# 2_digital_a.net
KiCad netlist of a schematic drawn in EAGLE
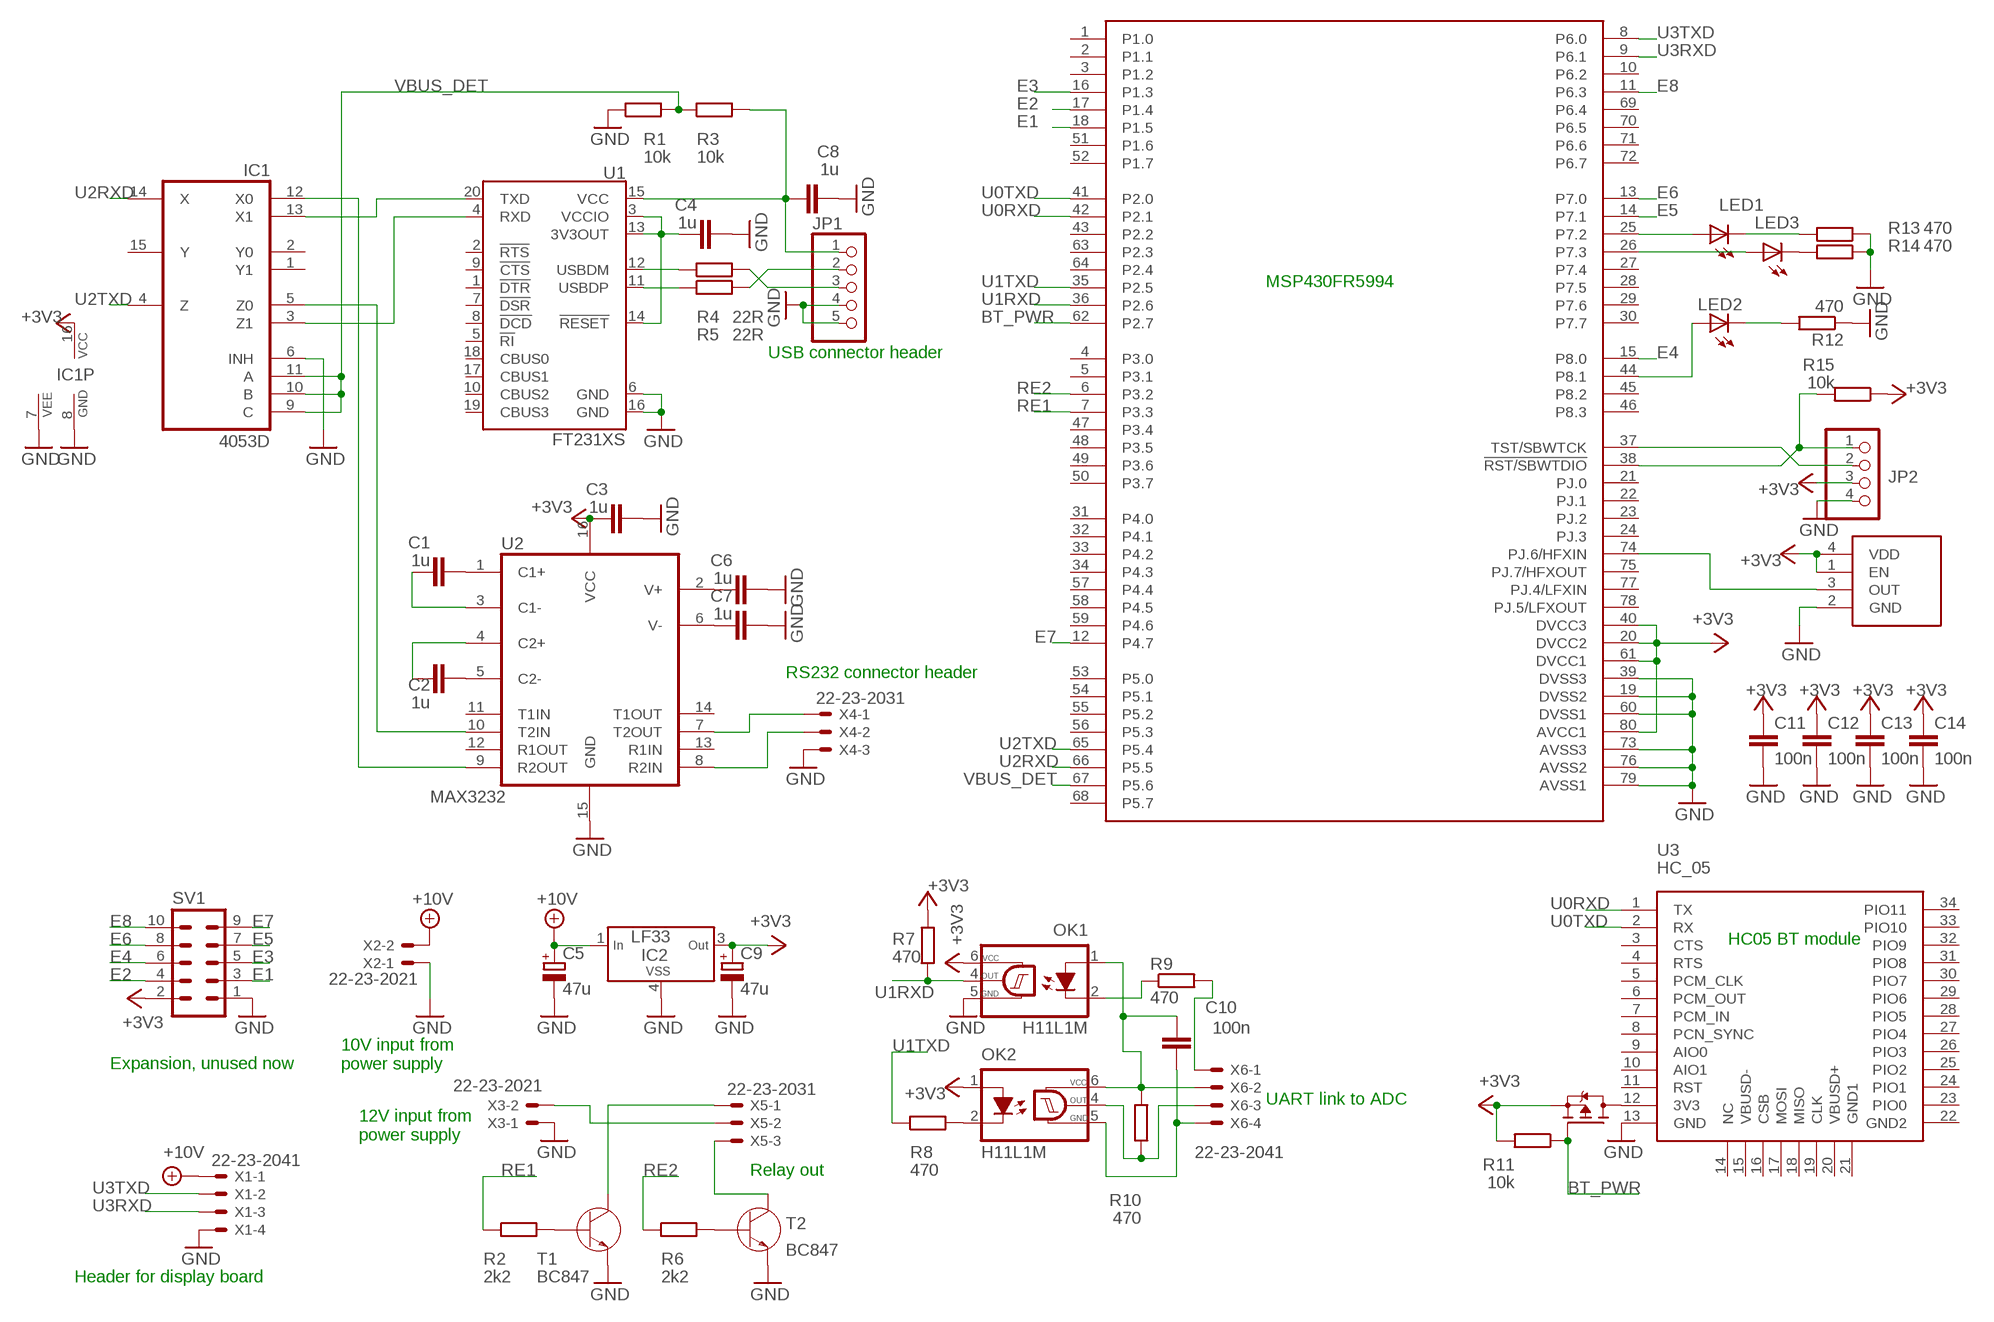
[diagram p0: schematic, sheet 1]

(export (version "E")
  (design (tool "Eeschema 10.0.6"))
  (components
    (comp (ref "C1")
      (value "1u")
      (footprint "eagle-import:R0805")
      (libsource (lib "eagle-import") (part "C_0806"))
    )
    (comp (ref "C2")
      (value "1u")
      (footprint "eagle-import:R0805")
      (libsource (lib "eagle-import") (part "C_0806"))
    )
    (comp (ref "C3")
      (value "1u")
      (footprint "eagle-import:R0805")
      (libsource (lib "eagle-import") (part "C_0806"))
    )
    (comp (ref "C4")
      (value "1u")
      (footprint "eagle-import:R0805")
      (libsource (lib "eagle-import") (part "C_0806"))
    )
    (comp (ref "C5")
      (value "47u")
      (footprint "eagle-import:SMC_C")
      (libsource (lib "eagle-import") (part "CPOL-EUSMCC"))
    )
    (comp (ref "C6")
      (value "1u")
      (footprint "eagle-import:R0805")
      (libsource (lib "eagle-import") (part "C_0806"))
    )
    (comp (ref "C7")
      (value "1u")
      (footprint "eagle-import:R0805")
      (libsource (lib "eagle-import") (part "C_0806"))
    )
    (comp (ref "C8")
      (value "1u")
      (footprint "eagle-import:R0805")
      (libsource (lib "eagle-import") (part "C_0806"))
    )
    (comp (ref "C9")
      (value "47u")
      (footprint "eagle-import:SMC_C")
      (libsource (lib "eagle-import") (part "CPOL-EUSMCC"))
    )
    (comp (ref "C10")
      (value "100n")
      (footprint "eagle-import:0603")
      (libsource (lib "eagle-import") (part "C_0603"))
    )
    (comp (ref "C11")
      (value "100n")
      (footprint "eagle-import:0603")
      (libsource (lib "eagle-import") (part "C_0603"))
    )
    (comp (ref "C12")
      (value "100n")
      (footprint "eagle-import:0603")
      (libsource (lib "eagle-import") (part "C_0603"))
    )
    (comp (ref "C13")
      (value "100n")
      (footprint "eagle-import:0603")
      (libsource (lib "eagle-import") (part "C_0603"))
    )
    (comp (ref "C14")
      (value "100n")
      (footprint "eagle-import:0603")
      (libsource (lib "eagle-import") (part "C_0603"))
    )
    (comp (ref "IC1")
      (value "4053D")
      (footprint "eagle-import:SO16")
      (libsource (lib "eagle-import") (part "4053D"))
    )
    (comp (ref "IC2")
      (value "LF33")
      (footprint "eagle-import:DPAK")
      (libsource (lib "eagle-import") (part "LF33-DPAK"))
    )
    (comp (ref "IC3")
      (value "MSP430FR5994")
      (footprint "eagle-import:QFP_05_80")
      (libsource (lib "eagle-import") (part "MSP430FR5994"))
    )
    (comp (ref "JP1")
      (value "PINHD-1X05_2.54")
      (footprint "eagle-import:1X05")
      (libsource (lib "eagle-import") (part "PINHD-1X05_2.54"))
    )
    (comp (ref "JP2")
      (value "PINHD-1X04_2.54")
      (footprint "eagle-import:1X04")
      (libsource (lib "eagle-import") (part "PINHD-1X04_2.54"))
    )
    (comp (ref "LED1")
      (value "LEDCHIPLED_0805")
      (footprint "eagle-import:CHIPLED_0805")
      (libsource (lib "eagle-import") (part "LEDCHIPLED_0805"))
    )
    (comp (ref "LED2")
      (value "LEDCHIPLED_0805")
      (footprint "eagle-import:CHIPLED_0805")
      (libsource (lib "eagle-import") (part "LEDCHIPLED_0805"))
    )
    (comp (ref "LED3")
      (value "LEDCHIPLED_0805")
      (footprint "eagle-import:CHIPLED_0805")
      (libsource (lib "eagle-import") (part "LEDCHIPLED_0805"))
    )
    (comp (ref "O1")
      (value "OSC5032")
      (footprint "eagle-import:OSC_5032")
      (libsource (lib "eagle-import") (part "OSC5032"))
    )
    (comp (ref "OK1")
      (value "H11L1M")
      (footprint "eagle-import:DIL06")
      (libsource (lib "eagle-import") (part "H11LM1"))
    )
    (comp (ref "OK2")
      (value "H11L1M")
      (footprint "eagle-import:DIL06")
      (libsource (lib "eagle-import") (part "H11LM1"))
    )
    (comp (ref "R1")
      (value "10k")
      (footprint "eagle-import:R0805")
      (libsource (lib "eagle-import") (part "R_0805"))
    )
    (comp (ref "R2")
      (value "2k2")
      (footprint "eagle-import:R0805")
      (libsource (lib "eagle-import") (part "R_0805"))
    )
    (comp (ref "R3")
      (value "10k")
      (footprint "eagle-import:R0805")
      (libsource (lib "eagle-import") (part "R_0805"))
    )
    (comp (ref "R4")
      (value "22R")
      (footprint "eagle-import:R0805")
      (libsource (lib "eagle-import") (part "R_0805"))
    )
    (comp (ref "R5")
      (value "22R")
      (footprint "eagle-import:R0805")
      (libsource (lib "eagle-import") (part "R_0805"))
    )
    (comp (ref "R6")
      (value "2k2")
      (footprint "eagle-import:R0805")
      (libsource (lib "eagle-import") (part "R_0805"))
    )
    (comp (ref "R7")
      (value "470")
      (footprint "eagle-import:R0805")
      (libsource (lib "eagle-import") (part "R_0805"))
    )
    (comp (ref "R8")
      (value "470")
      (footprint "eagle-import:R0805")
      (libsource (lib "eagle-import") (part "R_0805"))
    )
    (comp (ref "R9")
      (value "470")
      (footprint "eagle-import:R0805")
      (libsource (lib "eagle-import") (part "R_0805"))
    )
    (comp (ref "R10")
      (value "470")
      (footprint "eagle-import:R0805")
      (libsource (lib "eagle-import") (part "R_0805"))
    )
    (comp (ref "R11")
      (value "10k")
      (footprint "eagle-import:R0805")
      (libsource (lib "eagle-import") (part "R_0805"))
    )
    (comp (ref "R12")
      (value "470")
      (footprint "eagle-import:R0805")
      (libsource (lib "eagle-import") (part "R_0805"))
    )
    (comp (ref "R13")
      (value "470")
      (footprint "eagle-import:R0805")
      (libsource (lib "eagle-import") (part "R_0805"))
    )
    (comp (ref "R14")
      (value "470")
      (footprint "eagle-import:R0805")
      (libsource (lib "eagle-import") (part "R_0805"))
    )
    (comp (ref "R15")
      (value "10k")
      (footprint "eagle-import:R0805")
      (libsource (lib "eagle-import") (part "R_0805"))
    )
    (comp (ref "SV1")
      (value "ML10")
      (footprint "eagle-import:ML10")
      (libsource (lib "eagle-import") (part "ML10"))
    )
    (comp (ref "T1")
      (value "BC847")
      (footprint "eagle-import:SOT23")
      (libsource (lib "eagle-import") (part "BC847"))
    )
    (comp (ref "T2")
      (value "BC847")
      (footprint "eagle-import:SOT23")
      (libsource (lib "eagle-import") (part "BC847"))
    )
    (comp (ref "U$1")
      (value "Si2333")
      (footprint "eagle-import:SOT23-3")
      (libsource (lib "eagle-import") (part "BSS84"))
    )
    (comp (ref "U1")
      (value "FT231XS")
      (footprint "eagle-import:SSOP20_L")
      (libsource (lib "eagle-import") (part "FT231XS"))
    )
    (comp (ref "U2")
      (value "MAX3232")
      (footprint "eagle-import:SO016")
      (libsource (lib "eagle-import") (part "MAX232SOIC16"))
    )
    (comp (ref "U3")
      (value "HC_05")
      (footprint "eagle-import:BLUETOOTH_SMD")
      (libsource (lib "eagle-import") (part "HC_05"))
    )
    (comp (ref "X1")
      (value "22-23-2041")
      (footprint "eagle-import:22-23-2041")
      (fields (field (name "MF") "MOLEX"))
      (libsource (lib "eagle-import") (part "22-23-2041"))
    )
    (comp (ref "X2")
      (value "22-23-2021")
      (footprint "eagle-import:22-23-2021")
      (fields (field (name "MF") "MOLEX"))
      (libsource (lib "eagle-import") (part "22-23-2021"))
    )
    (comp (ref "X3")
      (value "22-23-2021")
      (footprint "eagle-import:22-23-2021")
      (fields (field (name "MF") "MOLEX"))
      (libsource (lib "eagle-import") (part "22-23-2021"))
    )
    (comp (ref "X4")
      (value "22-23-2031")
      (footprint "eagle-import:22-23-2031")
      (fields (field (name "MF") "MOLEX"))
      (libsource (lib "eagle-import") (part "22-23-2031"))
    )
    (comp (ref "X5")
      (value "22-23-2031")
      (footprint "eagle-import:22-23-2031")
      (fields (field (name "MF") "MOLEX"))
      (libsource (lib "eagle-import") (part "22-23-2031"))
    )
    (comp (ref "X6")
      (value "22-23-2041")
      (footprint "eagle-import:22-23-2041")
      (fields (field (name "MF") "MOLEX"))
      (libsource (lib "eagle-import") (part "22-23-2041"))
    )
  )
  (nets
    (net (code "1") (name "+3V3") (class "Default")
      (node (ref "C11") (pin "1") (pinfunction "1_1") (pintype "passive"))
      (node (ref "C12") (pin "1") (pinfunction "1_1") (pintype "passive"))
      (node (ref "C13") (pin "1") (pinfunction "1_1") (pintype "passive"))
      (node (ref "C14") (pin "1") (pinfunction "1_1") (pintype "passive"))
      (node (ref "C3") (pin "1") (pinfunction "1_1") (pintype "passive"))
      (node (ref "C9") (pin "+") (pinfunction "+_+") (pintype "passive"))
      (node (ref "IC1") (pin "16") (pinfunction "VCC_16") (pintype "power_in"))
      (node (ref "IC2") (pin "3") (pinfunction "OUT_3") (pintype "output"))
      (node (ref "IC3") (pin "20") (pinfunction "DVCC2_20") (pintype "bidirectional"))
      (node (ref "IC3") (pin "40") (pinfunction "DVCC3_40") (pintype "bidirectional"))
      (node (ref "IC3") (pin "61") (pinfunction "DVCC1_61") (pintype "bidirectional"))
      (node (ref "IC3") (pin "80") (pinfunction "AVCC1_80") (pintype "bidirectional"))
      (node (ref "JP2") (pin "3") (pinfunction "3_3") (pintype "passive"))
      (node (ref "O1") (pin "1") (pinfunction "EN_1") (pintype "bidirectional"))
      (node (ref "O1") (pin "4") (pinfunction "VDD_4") (pintype "bidirectional"))
      (node (ref "OK1") (pin "6") (pinfunction "VCC_6") (pintype "power_in"))
      (node (ref "OK2") (pin "1") (pinfunction "A_1") (pintype "passive"))
      (node (ref "R11") (pin "2") (pinfunction "2_2") (pintype "passive"))
      (node (ref "R15") (pin "1") (pinfunction "1_1") (pintype "passive"))
      (node (ref "R7") (pin "1") (pinfunction "1_1") (pintype "passive"))
      (node (ref "SV1") (pin "2") (pinfunction "2_2") (pintype "passive"))
      (node (ref "U$1") (pin "2") (pinfunction "S_2") (pintype "passive"))
      (node (ref "U2") (pin "16") (pinfunction "VCC_16") (pintype "bidirectional"))
    )
    (net (code "2") (name "+10V") (class "Default")
      (node (ref "C5") (pin "+") (pinfunction "+_+") (pintype "passive"))
      (node (ref "IC2") (pin "1") (pinfunction "IN_1") (pintype "input"))
      (node (ref "X1") (pin "1") (pinfunction "S_1") (pintype "passive"))
      (node (ref "X2") (pin "2") (pinfunction "S_2") (pintype "passive"))
    )
    (net (code "3") (name "/BT_PWR") (class "Default")
      (node (ref "IC3") (pin "62") (pinfunction "P2.7_62") (pintype "bidirectional"))
      (node (ref "R11") (pin "1") (pinfunction "1_1") (pintype "passive"))
      (node (ref "U$1") (pin "1") (pinfunction "G_1") (pintype "passive"))
    )
    (net (code "4") (name "/E1") (class "Default")
      (node (ref "IC3") (pin "18") (pinfunction "P1.5_18") (pintype "bidirectional"))
      (node (ref "SV1") (pin "3") (pinfunction "3_3") (pintype "passive"))
    )
    (net (code "5") (name "/E2") (class "Default")
      (node (ref "IC3") (pin "17") (pinfunction "P1.4_17") (pintype "bidirectional"))
      (node (ref "SV1") (pin "4") (pinfunction "4_4") (pintype "passive"))
    )
    (net (code "6") (name "/E3") (class "Default")
      (node (ref "IC3") (pin "16") (pinfunction "P1.3_16") (pintype "bidirectional"))
      (node (ref "SV1") (pin "5") (pinfunction "5_5") (pintype "passive"))
    )
    (net (code "7") (name "/E4") (class "Default")
      (node (ref "IC3") (pin "15") (pinfunction "P8.0_15") (pintype "bidirectional"))
      (node (ref "SV1") (pin "6") (pinfunction "6_6") (pintype "passive"))
    )
    (net (code "8") (name "/E5") (class "Default")
      (node (ref "IC3") (pin "14") (pinfunction "P7.1_14") (pintype "bidirectional"))
      (node (ref "SV1") (pin "7") (pinfunction "7_7") (pintype "passive"))
    )
    (net (code "9") (name "/E6") (class "Default")
      (node (ref "IC3") (pin "13") (pinfunction "P7.0_13") (pintype "bidirectional"))
      (node (ref "SV1") (pin "8") (pinfunction "8_8") (pintype "passive"))
    )
    (net (code "10") (name "/E7") (class "Default")
      (node (ref "IC3") (pin "12") (pinfunction "P4.7_12") (pintype "bidirectional"))
      (node (ref "SV1") (pin "9") (pinfunction "9_9") (pintype "passive"))
    )
    (net (code "11") (name "/E8") (class "Default")
      (node (ref "IC3") (pin "11") (pinfunction "P6.3_11") (pintype "bidirectional"))
      (node (ref "SV1") (pin "10") (pinfunction "10_10") (pintype "passive"))
    )
    (net (code "12") (name "/RE1") (class "Default")
      (node (ref "IC3") (pin "7") (pinfunction "P3.3_7") (pintype "bidirectional"))
      (node (ref "R2") (pin "1") (pinfunction "1_1") (pintype "passive"))
    )
    (net (code "13") (name "/RE2") (class "Default")
      (node (ref "IC3") (pin "6") (pinfunction "P3.2_6") (pintype "bidirectional"))
      (node (ref "R6") (pin "1") (pinfunction "1_1") (pintype "passive"))
    )
    (net (code "14") (name "/U0RXD") (class "Default")
      (node (ref "IC3") (pin "42") (pinfunction "P2.1_42") (pintype "bidirectional"))
      (node (ref "U3") (pin "1") (pinfunction "TX_1") (pintype "bidirectional"))
    )
    (net (code "15") (name "/U0TXD") (class "Default")
      (node (ref "IC3") (pin "41") (pinfunction "P2.0_41") (pintype "bidirectional"))
      (node (ref "U3") (pin "2") (pinfunction "RX_2") (pintype "bidirectional"))
    )
    (net (code "16") (name "/U1RXD") (class "Default")
      (node (ref "IC3") (pin "36") (pinfunction "P2.6_36") (pintype "bidirectional"))
      (node (ref "OK1") (pin "4") (pinfunction "OUT_4") (pintype "output"))
      (node (ref "R7") (pin "2") (pinfunction "2_2") (pintype "passive"))
    )
    (net (code "17") (name "/U1TXD") (class "Default")
      (node (ref "IC3") (pin "35") (pinfunction "P2.5_35") (pintype "bidirectional"))
      (node (ref "R8") (pin "1") (pinfunction "1_1") (pintype "passive"))
    )
    (net (code "18") (name "/U2RXD") (class "Default")
      (node (ref "IC1") (pin "14") (pinfunction "X_14") (pintype "bidirectional"))
      (node (ref "IC3") (pin "66") (pinfunction "P5.5_66") (pintype "bidirectional"))
    )
    (net (code "19") (name "/U2TXD") (class "Default")
      (node (ref "IC1") (pin "4") (pinfunction "Z_4") (pintype "bidirectional"))
      (node (ref "IC3") (pin "65") (pinfunction "P5.4_65") (pintype "bidirectional"))
    )
    (net (code "20") (name "/U3RXD") (class "Default")
      (node (ref "IC3") (pin "9") (pinfunction "P6.1_9") (pintype "bidirectional"))
      (node (ref "X1") (pin "3") (pinfunction "S_3") (pintype "passive"))
    )
    (net (code "21") (name "/U3TXD") (class "Default")
      (node (ref "IC3") (pin "8") (pinfunction "P6.0_8") (pintype "bidirectional"))
      (node (ref "X1") (pin "2") (pinfunction "S_2") (pintype "passive"))
    )
    (net (code "22") (name "/VBUS_DET") (class "Default")
      (node (ref "IC1") (pin "10") (pinfunction "B_10") (pintype "input"))
      (node (ref "IC1") (pin "11") (pinfunction "A_11") (pintype "input"))
      (node (ref "IC1") (pin "9") (pinfunction "C_9") (pintype "input"))
      (node (ref "IC3") (pin "67") (pinfunction "P5.6_67") (pintype "bidirectional"))
      (node (ref "R1") (pin "2") (pinfunction "2_2") (pintype "passive"))
      (node (ref "R3") (pin "1") (pinfunction "1_1") (pintype "passive"))
    )
    (net (code "23") (name "GND") (class "Default")
      (node (ref "C11") (pin "2") (pinfunction "2_2") (pintype "passive"))
      (node (ref "C12") (pin "2") (pinfunction "2_2") (pintype "passive"))
      (node (ref "C13") (pin "2") (pinfunction "2_2") (pintype "passive"))
      (node (ref "C14") (pin "2") (pinfunction "2_2") (pintype "passive"))
      (node (ref "C3") (pin "2") (pinfunction "2_2") (pintype "passive"))
      (node (ref "C4") (pin "2") (pinfunction "2_2") (pintype "passive"))
      (node (ref "C5") (pin "-") (pinfunction "-_-") (pintype "passive"))
      (node (ref "C6") (pin "2") (pinfunction "2_2") (pintype "passive"))
      (node (ref "C7") (pin "2") (pinfunction "2_2") (pintype "passive"))
      (node (ref "C8") (pin "2") (pinfunction "2_2") (pintype "passive"))
      (node (ref "C9") (pin "-") (pinfunction "-_-") (pintype "passive"))
      (node (ref "IC1") (pin "6") (pinfunction "INH_6") (pintype "input"))
      (node (ref "IC1") (pin "7") (pinfunction "VEE_7") (pintype "power_in"))
      (node (ref "IC1") (pin "8") (pinfunction "GND_8") (pintype "power_in"))
      (node (ref "IC2") (pin "4") (pinfunction "VSS_4") (pintype "input"))
      (node (ref "IC3") (pin "19") (pinfunction "DVSS2_19") (pintype "bidirectional"))
      (node (ref "IC3") (pin "39") (pinfunction "DVSS3_39") (pintype "bidirectional"))
      (node (ref "IC3") (pin "60") (pinfunction "DVSS1_60") (pintype "bidirectional"))
      (node (ref "IC3") (pin "73") (pinfunction "AVSS3_73") (pintype "bidirectional"))
      (node (ref "IC3") (pin "76") (pinfunction "AVSS2_76") (pintype "bidirectional"))
      (node (ref "IC3") (pin "79") (pinfunction "AVSS1_79") (pintype "bidirectional"))
      (node (ref "JP1") (pin "4") (pinfunction "4_4") (pintype "passive"))
      (node (ref "JP1") (pin "5") (pinfunction "5_5") (pintype "passive"))
      (node (ref "JP2") (pin "4") (pinfunction "4_4") (pintype "passive"))
      (node (ref "O1") (pin "2") (pinfunction "GND_2") (pintype "bidirectional"))
      (node (ref "OK1") (pin "5") (pinfunction "GND_5") (pintype "power_in"))
      (node (ref "R1") (pin "1") (pinfunction "1_1") (pintype "passive"))
      (node (ref "R12") (pin "1") (pinfunction "1_1") (pintype "passive"))
      (node (ref "R13") (pin "1") (pinfunction "1_1") (pintype "passive"))
      (node (ref "R14") (pin "1") (pinfunction "1_1") (pintype "passive"))
      (node (ref "SV1") (pin "1") (pinfunction "1_1") (pintype "passive"))
      (node (ref "T1") (pin "2") (pinfunction "E_2") (pintype "passive"))
      (node (ref "T2") (pin "2") (pinfunction "E_2") (pintype "passive"))
      (node (ref "U1") (pin "16") (pinfunction "GND_16") (pintype "bidirectional"))
      (node (ref "U1") (pin "6") (pinfunction "GND_6") (pintype "bidirectional"))
      (node (ref "U2") (pin "15") (pinfunction "GND_15") (pintype "bidirectional"))
      (node (ref "U3") (pin "13") (pinfunction "GND_13") (pintype "bidirectional"))
      (node (ref "X1") (pin "4") (pinfunction "S_4") (pintype "passive"))
      (node (ref "X2") (pin "1") (pinfunction "S_1") (pintype "passive"))
      (node (ref "X3") (pin "1") (pinfunction "S_1") (pintype "passive"))
      (node (ref "X4") (pin "3") (pinfunction "S_3") (pintype "passive"))
    )
    (net (code "24") (name "Net-(IC1A-X0)") (class "Default")
      (node (ref "IC1") (pin "12") (pinfunction "X0_12") (pintype "bidirectional"))
      (node (ref "U2") (pin "9") (pinfunction "R2OUT_9") (pintype "output"))
    )
    (net (code "25") (name "Net-(IC1A-X1)") (class "Default")
      (node (ref "IC1") (pin "13") (pinfunction "X1_13") (pintype "bidirectional"))
      (node (ref "U1") (pin "20") (pinfunction "TXD_20") (pintype "bidirectional"))
    )
    (net (code "26") (name "Net-(IC1A-Z0)") (class "Default")
      (node (ref "IC1") (pin "5") (pinfunction "Z0_5") (pintype "bidirectional"))
      (node (ref "U2") (pin "10") (pinfunction "T2IN_10") (pintype "input"))
    )
    (net (code "27") (name "Net-(IC1A-Z1)") (class "Default")
      (node (ref "IC1") (pin "3") (pinfunction "Z1_3") (pintype "bidirectional"))
      (node (ref "U1") (pin "4") (pinfunction "RXD_4") (pintype "bidirectional"))
    )
    (net (code "28") (name "Net-(IC3-P7.2)") (class "Default")
      (node (ref "IC3") (pin "25") (pinfunction "P7.2_25") (pintype "bidirectional"))
      (node (ref "LED1") (pin "A") (pinfunction "A_A") (pintype "passive"))
    )
    (net (code "29") (name "Net-(IC3-P7.3)") (class "Default")
      (node (ref "IC3") (pin "26") (pinfunction "P7.3_26") (pintype "bidirectional"))
      (node (ref "LED3") (pin "A") (pinfunction "A_A") (pintype "passive"))
    )
    (net (code "30") (name "Net-(IC3-P8.1)") (class "Default")
      (node (ref "IC3") (pin "44") (pinfunction "P8.1_44") (pintype "bidirectional"))
      (node (ref "LED2") (pin "A") (pinfunction "A_A") (pintype "passive"))
    )
    (net (code "31") (name "Net-(IC3-PJ.6{slash}HFXIN)") (class "Default")
      (node (ref "IC3") (pin "74") (pinfunction "PJ.6/HFXIN_74") (pintype "bidirectional"))
      (node (ref "O1") (pin "3") (pinfunction "OUT_3") (pintype "bidirectional"))
    )
    (net (code "32") (name "Net-(IC3-TST{slash}SBWTCK)") (class "Default")
      (node (ref "IC3") (pin "37") (pinfunction "TST/SBWTCK_37") (pintype "bidirectional"))
      (node (ref "JP2") (pin "2") (pinfunction "2_2") (pintype "passive"))
    )
    (net (code "33") (name "Net-(IC3-~{RST{slash}SBWTDIO})") (class "Default")
      (node (ref "IC3") (pin "38") (pinfunction "~{RST/SBWTDIO}_38") (pintype "bidirectional"))
      (node (ref "JP2") (pin "1") (pinfunction "1_1") (pintype "passive"))
      (node (ref "R15") (pin "2") (pinfunction "2_2") (pintype "passive"))
    )
    (net (code "34") (name "Net-(JP1-Pad2)") (class "Default")
      (node (ref "JP1") (pin "2") (pinfunction "2_2") (pintype "passive"))
      (node (ref "R5") (pin "2") (pinfunction "2_2") (pintype "passive"))
    )
    (net (code "35") (name "Net-(JP1-Pad3)") (class "Default")
      (node (ref "JP1") (pin "3") (pinfunction "3_3") (pintype "passive"))
      (node (ref "R4") (pin "2") (pinfunction "2_2") (pintype "passive"))
    )
    (net (code "36") (name "Net-(LED1-PadC)") (class "Default")
      (node (ref "LED1") (pin "C") (pinfunction "C_C") (pintype "passive"))
      (node (ref "R13") (pin "2") (pinfunction "2_2") (pintype "passive"))
    )
    (net (code "37") (name "Net-(LED2-PadC)") (class "Default")
      (node (ref "LED2") (pin "C") (pinfunction "C_C") (pintype "passive"))
      (node (ref "R12") (pin "2") (pinfunction "2_2") (pintype "passive"))
    )
    (net (code "38") (name "Net-(LED3-PadC)") (class "Default")
      (node (ref "LED3") (pin "C") (pinfunction "C_C") (pintype "passive"))
      (node (ref "R14") (pin "2") (pinfunction "2_2") (pintype "passive"))
    )
    (net (code "39") (name "Net-(OK1-A)") (class "Default")
      (node (ref "C10") (pin "1") (pinfunction "1_1") (pintype "passive"))
      (node (ref "OK1") (pin "1") (pinfunction "A_1") (pintype "passive"))
      (node (ref "OK2") (pin "6") (pinfunction "VCC_6") (pintype "power_in"))
      (node (ref "R10") (pin "2") (pinfunction "2_2") (pintype "passive"))
      (node (ref "X6") (pin "2") (pinfunction "S_2") (pintype "passive"))
    )
    (net (code "40") (name "Net-(OK1-C)") (class "Default")
      (node (ref "OK1") (pin "2") (pinfunction "C_2") (pintype "passive"))
      (node (ref "R9") (pin "1") (pinfunction "1_1") (pintype "passive"))
    )
    (net (code "41") (name "Net-(OK2-C)") (class "Default")
      (node (ref "OK2") (pin "2") (pinfunction "C_2") (pintype "passive"))
      (node (ref "R8") (pin "2") (pinfunction "2_2") (pintype "passive"))
    )
    (net (code "42") (name "Net-(OK2-GND)") (class "Default")
      (node (ref "C10") (pin "2") (pinfunction "2_2") (pintype "passive"))
      (node (ref "OK2") (pin "5") (pinfunction "GND_5") (pintype "power_in"))
      (node (ref "X6") (pin "4") (pinfunction "S_4") (pintype "passive"))
    )
    (net (code "43") (name "Net-(OK2-OUT)") (class "Default")
      (node (ref "OK2") (pin "4") (pinfunction "OUT_4") (pintype "output"))
      (node (ref "R10") (pin "1") (pinfunction "1_1") (pintype "passive"))
      (node (ref "X6") (pin "3") (pinfunction "S_3") (pintype "passive"))
    )
    (net (code "44") (name "Net-(T1-B)") (class "Default")
      (node (ref "R2") (pin "2") (pinfunction "2_2") (pintype "passive"))
      (node (ref "T1") (pin "1") (pinfunction "B_1") (pintype "passive"))
    )
    (net (code "45") (name "Net-(T1-C)") (class "Default")
      (node (ref "T1") (pin "3") (pinfunction "C_3") (pintype "passive"))
      (node (ref "X5") (pin "1") (pinfunction "S_1") (pintype "passive"))
    )
    (net (code "46") (name "Net-(T2-B)") (class "Default")
      (node (ref "R6") (pin "2") (pinfunction "2_2") (pintype "passive"))
      (node (ref "T2") (pin "1") (pinfunction "B_1") (pintype "passive"))
    )
    (net (code "47") (name "Net-(T2-C)") (class "Default")
      (node (ref "T2") (pin "3") (pinfunction "C_3") (pintype "passive"))
      (node (ref "X5") (pin "3") (pinfunction "S_3") (pintype "passive"))
    )
    (net (code "48") (name "Net-(U$1-D)") (class "Default")
      (node (ref "U$1") (pin "3") (pinfunction "D_3") (pintype "passive"))
      (node (ref "U3") (pin "12") (pinfunction "3V3_12") (pintype "bidirectional"))
    )
    (net (code "49") (name "Net-(U1-3V3OUT)") (class "Default")
      (node (ref "C4") (pin "1") (pinfunction "1_1") (pintype "passive"))
      (node (ref "U1") (pin "13") (pinfunction "3V3OUT_13") (pintype "bidirectional"))
      (node (ref "U1") (pin "14") (pinfunction "~{RESET}_14") (pintype "bidirectional"))
      (node (ref "U1") (pin "3") (pinfunction "VCCIO_3") (pintype "bidirectional"))
    )
    (net (code "50") (name "Net-(U1-USBDM)") (class "Default")
      (node (ref "R4") (pin "1") (pinfunction "1_1") (pintype "passive"))
      (node (ref "U1") (pin "12") (pinfunction "USBDM_12") (pintype "bidirectional"))
    )
    (net (code "51") (name "Net-(U1-USBDP)") (class "Default")
      (node (ref "R5") (pin "1") (pinfunction "1_1") (pintype "passive"))
      (node (ref "U1") (pin "11") (pinfunction "USBDP_11") (pintype "bidirectional"))
    )
    (net (code "52") (name "Net-(U1-VCC)") (class "Default")
      (node (ref "C8") (pin "1") (pinfunction "1_1") (pintype "passive"))
      (node (ref "JP1") (pin "1") (pinfunction "1_1") (pintype "passive"))
      (node (ref "R3") (pin "2") (pinfunction "2_2") (pintype "passive"))
      (node (ref "U1") (pin "15") (pinfunction "VCC_15") (pintype "bidirectional"))
    )
    (net (code "53") (name "Net-(U2-C1+)") (class "Default")
      (node (ref "C1") (pin "2") (pinfunction "2_2") (pintype "passive"))
      (node (ref "U2") (pin "1") (pinfunction "C1+_1") (pintype "bidirectional"))
    )
    (net (code "54") (name "Net-(U2-C1-)") (class "Default")
      (node (ref "C1") (pin "1") (pinfunction "1_1") (pintype "passive"))
      (node (ref "U2") (pin "3") (pinfunction "C1-_3") (pintype "bidirectional"))
    )
    (net (code "55") (name "Net-(U2-C2+)") (class "Default")
      (node (ref "C2") (pin "1") (pinfunction "1_1") (pintype "passive"))
      (node (ref "U2") (pin "4") (pinfunction "C2+_4") (pintype "bidirectional"))
    )
    (net (code "56") (name "Net-(U2-C2-)") (class "Default")
      (node (ref "C2") (pin "2") (pinfunction "2_2") (pintype "passive"))
      (node (ref "U2") (pin "5") (pinfunction "C2-_5") (pintype "bidirectional"))
    )
    (net (code "57") (name "Net-(U2-R2IN)") (class "Default")
      (node (ref "U2") (pin "8") (pinfunction "R2IN_8") (pintype "input"))
      (node (ref "X4") (pin "2") (pinfunction "S_2") (pintype "passive"))
    )
    (net (code "58") (name "Net-(U2-T2OUT)") (class "Default")
      (node (ref "U2") (pin "7") (pinfunction "T2OUT_7") (pintype "output"))
      (node (ref "X4") (pin "1") (pinfunction "S_1") (pintype "passive"))
    )
    (net (code "59") (name "Net-(U2-V+)") (class "Default")
      (node (ref "C6") (pin "1") (pinfunction "1_1") (pintype "passive"))
      (node (ref "U2") (pin "2") (pinfunction "V+_2") (pintype "bidirectional"))
    )
    (net (code "60") (name "Net-(U2-V-)") (class "Default")
      (node (ref "C7") (pin "1") (pinfunction "1_1") (pintype "passive"))
      (node (ref "U2") (pin "6") (pinfunction "V-_6") (pintype "bidirectional"))
    )
    (net (code "61") (name "Net-(X3B-S)") (class "Default")
      (node (ref "X3") (pin "2") (pinfunction "S_2") (pintype "passive"))
      (node (ref "X5") (pin "2") (pinfunction "S_2") (pintype "passive"))
    )
    (net (code "62") (name "Net-(X6A-S)") (class "Default")
      (node (ref "R9") (pin "2") (pinfunction "2_2") (pintype "passive"))
      (node (ref "X6") (pin "1") (pinfunction "S_1") (pintype "passive"))
    )
    (net (code "63") (name "unconnected-(IC1A-Y-Pad15)") (class "Default")
      (node (ref "IC1") (pin "15") (pinfunction "Y_15") (pintype "bidirectional"))
    )
    (net (code "64") (name "unconnected-(IC1A-Y0-Pad2)") (class "Default")
      (node (ref "IC1") (pin "2") (pinfunction "Y0_2") (pintype "bidirectional"))
    )
    (net (code "65") (name "unconnected-(IC1A-Y1-Pad1)") (class "Default")
      (node (ref "IC1") (pin "1") (pinfunction "Y1_1") (pintype "bidirectional"))
    )
    (net (code "66") (name "unconnected-(IC3-P1.0-Pad1)") (class "Default")
      (node (ref "IC3") (pin "1") (pinfunction "P1.0_1") (pintype "bidirectional"))
    )
    (net (code "67") (name "unconnected-(IC3-P1.1-Pad2)") (class "Default")
      (node (ref "IC3") (pin "2") (pinfunction "P1.1_2") (pintype "bidirectional"))
    )
    (net (code "68") (name "unconnected-(IC3-P1.2-Pad3)") (class "Default")
      (node (ref "IC3") (pin "3") (pinfunction "P1.2_3") (pintype "bidirectional"))
    )
    (net (code "69") (name "unconnected-(IC3-P1.6-Pad51)") (class "Default")
      (node (ref "IC3") (pin "51") (pinfunction "P1.6_51") (pintype "bidirectional"))
    )
    (net (code "70") (name "unconnected-(IC3-P1.7-Pad52)") (class "Default")
      (node (ref "IC3") (pin "52") (pinfunction "P1.7_52") (pintype "bidirectional"))
    )
    (net (code "71") (name "unconnected-(IC3-P2.2-Pad43)") (class "Default")
      (node (ref "IC3") (pin "43") (pinfunction "P2.2_43") (pintype "bidirectional"))
    )
    (net (code "72") (name "unconnected-(IC3-P2.3-Pad63)") (class "Default")
      (node (ref "IC3") (pin "63") (pinfunction "P2.3_63") (pintype "bidirectional"))
    )
    (net (code "73") (name "unconnected-(IC3-P2.4-Pad64)") (class "Default")
      (node (ref "IC3") (pin "64") (pinfunction "P2.4_64") (pintype "bidirectional"))
    )
    (net (code "74") (name "unconnected-(IC3-P3.0-Pad4)") (class "Default")
      (node (ref "IC3") (pin "4") (pinfunction "P3.0_4") (pintype "bidirectional"))
    )
    (net (code "75") (name "unconnected-(IC3-P3.1-Pad5)") (class "Default")
      (node (ref "IC3") (pin "5") (pinfunction "P3.1_5") (pintype "bidirectional"))
    )
    (net (code "76") (name "unconnected-(IC3-P3.4-Pad47)") (class "Default")
      (node (ref "IC3") (pin "47") (pinfunction "P3.4_47") (pintype "bidirectional"))
    )
    (net (code "77") (name "unconnected-(IC3-P3.5-Pad48)") (class "Default")
      (node (ref "IC3") (pin "48") (pinfunction "P3.5_48") (pintype "bidirectional"))
    )
    (net (code "78") (name "unconnected-(IC3-P3.6-Pad49)") (class "Default")
      (node (ref "IC3") (pin "49") (pinfunction "P3.6_49") (pintype "bidirectional"))
    )
    (net (code "79") (name "unconnected-(IC3-P3.7-Pad50)") (class "Default")
      (node (ref "IC3") (pin "50") (pinfunction "P3.7_50") (pintype "bidirectional"))
    )
    (net (code "80") (name "unconnected-(IC3-P4.0-Pad31)") (class "Default")
      (node (ref "IC3") (pin "31") (pinfunction "P4.0_31") (pintype "bidirectional"))
    )
    (net (code "81") (name "unconnected-(IC3-P4.1-Pad32)") (class "Default")
      (node (ref "IC3") (pin "32") (pinfunction "P4.1_32") (pintype "bidirectional"))
    )
    (net (code "82") (name "unconnected-(IC3-P4.2-Pad33)") (class "Default")
      (node (ref "IC3") (pin "33") (pinfunction "P4.2_33") (pintype "bidirectional"))
    )
    (net (code "83") (name "unconnected-(IC3-P4.3-Pad34)") (class "Default")
      (node (ref "IC3") (pin "34") (pinfunction "P4.3_34") (pintype "bidirectional"))
    )
    (net (code "84") (name "unconnected-(IC3-P4.4-Pad57)") (class "Default")
      (node (ref "IC3") (pin "57") (pinfunction "P4.4_57") (pintype "bidirectional"))
    )
    (net (code "85") (name "unconnected-(IC3-P4.5-Pad58)") (class "Default")
      (node (ref "IC3") (pin "58") (pinfunction "P4.5_58") (pintype "bidirectional"))
    )
    (net (code "86") (name "unconnected-(IC3-P4.6-Pad59)") (class "Default")
      (node (ref "IC3") (pin "59") (pinfunction "P4.6_59") (pintype "bidirectional"))
    )
    (net (code "87") (name "unconnected-(IC3-P5.0-Pad53)") (class "Default")
      (node (ref "IC3") (pin "53") (pinfunction "P5.0_53") (pintype "bidirectional"))
    )
    (net (code "88") (name "unconnected-(IC3-P5.1-Pad54)") (class "Default")
      (node (ref "IC3") (pin "54") (pinfunction "P5.1_54") (pintype "bidirectional"))
    )
    (net (code "89") (name "unconnected-(IC3-P5.2-Pad55)") (class "Default")
      (node (ref "IC3") (pin "55") (pinfunction "P5.2_55") (pintype "bidirectional"))
    )
    (net (code "90") (name "unconnected-(IC3-P5.3-Pad56)") (class "Default")
      (node (ref "IC3") (pin "56") (pinfunction "P5.3_56") (pintype "bidirectional"))
    )
    (net (code "91") (name "unconnected-(IC3-P5.7-Pad68)") (class "Default")
      (node (ref "IC3") (pin "68") (pinfunction "P5.7_68") (pintype "bidirectional"))
    )
    (net (code "92") (name "unconnected-(IC3-P6.2-Pad10)") (class "Default")
      (node (ref "IC3") (pin "10") (pinfunction "P6.2_10") (pintype "bidirectional"))
    )
    (net (code "93") (name "unconnected-(IC3-P6.4-Pad69)") (class "Default")
      (node (ref "IC3") (pin "69") (pinfunction "P6.4_69") (pintype "bidirectional"))
    )
    (net (code "94") (name "unconnected-(IC3-P6.5-Pad70)") (class "Default")
      (node (ref "IC3") (pin "70") (pinfunction "P6.5_70") (pintype "bidirectional"))
    )
    (net (code "95") (name "unconnected-(IC3-P6.6-Pad71)") (class "Default")
      (node (ref "IC3") (pin "71") (pinfunction "P6.6_71") (pintype "bidirectional"))
    )
    (net (code "96") (name "unconnected-(IC3-P6.7-Pad72)") (class "Default")
      (node (ref "IC3") (pin "72") (pinfunction "P6.7_72") (pintype "bidirectional"))
    )
    (net (code "97") (name "unconnected-(IC3-P7.4-Pad27)") (class "Default")
      (node (ref "IC3") (pin "27") (pinfunction "P7.4_27") (pintype "bidirectional"))
    )
    (net (code "98") (name "unconnected-(IC3-P7.5-Pad28)") (class "Default")
      (node (ref "IC3") (pin "28") (pinfunction "P7.5_28") (pintype "bidirectional"))
    )
    (net (code "99") (name "unconnected-(IC3-P7.6-Pad29)") (class "Default")
      (node (ref "IC3") (pin "29") (pinfunction "P7.6_29") (pintype "bidirectional"))
    )
    (net (code "100") (name "unconnected-(IC3-P7.7-Pad30)") (class "Default")
      (node (ref "IC3") (pin "30") (pinfunction "P7.7_30") (pintype "bidirectional"))
    )
    (net (code "101") (name "unconnected-(IC3-P8.2-Pad45)") (class "Default")
      (node (ref "IC3") (pin "45") (pinfunction "P8.2_45") (pintype "bidirectional"))
    )
    (net (code "102") (name "unconnected-(IC3-P8.3-Pad46)") (class "Default")
      (node (ref "IC3") (pin "46") (pinfunction "P8.3_46") (pintype "bidirectional"))
    )
    (net (code "103") (name "unconnected-(IC3-PJ.0-Pad21)") (class "Default")
      (node (ref "IC3") (pin "21") (pinfunction "PJ.0_21") (pintype "bidirectional"))
    )
    (net (code "104") (name "unconnected-(IC3-PJ.1-Pad22)") (class "Default")
      (node (ref "IC3") (pin "22") (pinfunction "PJ.1_22") (pintype "bidirectional"))
    )
    (net (code "105") (name "unconnected-(IC3-PJ.2-Pad23)") (class "Default")
      (node (ref "IC3") (pin "23") (pinfunction "PJ.2_23") (pintype "bidirectional"))
    )
    (net (code "106") (name "unconnected-(IC3-PJ.3-Pad24)") (class "Default")
      (node (ref "IC3") (pin "24") (pinfunction "PJ.3_24") (pintype "bidirectional"))
    )
    (net (code "107") (name "unconnected-(IC3-PJ.4{slash}LFXIN-Pad77)") (class "Default")
      (node (ref "IC3") (pin "77") (pinfunction "PJ.4/LFXIN_77") (pintype "bidirectional"))
    )
    (net (code "108") (name "unconnected-(IC3-PJ.5{slash}LFXOUT-Pad78)") (class "Default")
      (node (ref "IC3") (pin "78") (pinfunction "PJ.5/LFXOUT_78") (pintype "bidirectional"))
    )
    (net (code "109") (name "unconnected-(IC3-PJ.7{slash}HFXOUT-Pad75)") (class "Default")
      (node (ref "IC3") (pin "75") (pinfunction "PJ.7/HFXOUT_75") (pintype "bidirectional"))
    )
    (net (code "110") (name "unconnected-(U1-CBUS0-Pad18)") (class "Default")
      (node (ref "U1") (pin "18") (pinfunction "CBUS0_18") (pintype "bidirectional"))
    )
    (net (code "111") (name "unconnected-(U1-CBUS1-Pad17)") (class "Default")
      (node (ref "U1") (pin "17") (pinfunction "CBUS1_17") (pintype "bidirectional"))
    )
    (net (code "112") (name "unconnected-(U1-CBUS2-Pad10)") (class "Default")
      (node (ref "U1") (pin "10") (pinfunction "CBUS2_10") (pintype "bidirectional"))
    )
    (net (code "113") (name "unconnected-(U1-CBUS3-Pad19)") (class "Default")
      (node (ref "U1") (pin "19") (pinfunction "CBUS3_19") (pintype "bidirectional"))
    )
    (net (code "114") (name "unconnected-(U1-~{CTS}-Pad9)") (class "Default")
      (node (ref "U1") (pin "9") (pinfunction "~{CTS}_9") (pintype "bidirectional"))
    )
    (net (code "115") (name "unconnected-(U1-~{DCD}-Pad8)") (class "Default")
      (node (ref "U1") (pin "8") (pinfunction "~{DCD}_8") (pintype "bidirectional"))
    )
    (net (code "116") (name "unconnected-(U1-~{DSR}-Pad7)") (class "Default")
      (node (ref "U1") (pin "7") (pinfunction "~{DSR}_7") (pintype "bidirectional"))
    )
    (net (code "117") (name "unconnected-(U1-~{DTR}-Pad1)") (class "Default")
      (node (ref "U1") (pin "1") (pinfunction "~{DTR}_1") (pintype "bidirectional"))
    )
    (net (code "118") (name "unconnected-(U1-~{RI}-Pad5)") (class "Default")
      (node (ref "U1") (pin "5") (pinfunction "~{RI}_5") (pintype "bidirectional"))
    )
    (net (code "119") (name "unconnected-(U1-~{RTS}-Pad2)") (class "Default")
      (node (ref "U1") (pin "2") (pinfunction "~{RTS}_2") (pintype "bidirectional"))
    )
    (net (code "120") (name "unconnected-(U2-R1IN-Pad13)") (class "Default")
      (node (ref "U2") (pin "13") (pinfunction "R1IN_13") (pintype "input"))
    )
    (net (code "121") (name "unconnected-(U2-R1OUT-Pad12)") (class "Default")
      (node (ref "U2") (pin "12") (pinfunction "R1OUT_12") (pintype "output"))
    )
    (net (code "122") (name "unconnected-(U2-T1IN-Pad11)") (class "Default")
      (node (ref "U2") (pin "11") (pinfunction "T1IN_11") (pintype "input"))
    )
    (net (code "123") (name "unconnected-(U2-T1OUT-Pad14)") (class "Default")
      (node (ref "U2") (pin "14") (pinfunction "T1OUT_14") (pintype "output"))
    )
    (net (code "124") (name "unconnected-(U3-AIO0-Pad9)") (class "Default")
      (node (ref "U3") (pin "9") (pinfunction "AIO0_9") (pintype "bidirectional"))
    )
    (net (code "125") (name "unconnected-(U3-AIO1-Pad10)") (class "Default")
      (node (ref "U3") (pin "10") (pinfunction "AIO1_10") (pintype "bidirectional"))
    )
    (net (code "126") (name "unconnected-(U3-CLK-Pad19)") (class "Default")
      (node (ref "U3") (pin "19") (pinfunction "CLK_19") (pintype "bidirectional"))
    )
    (net (code "127") (name "unconnected-(U3-CSB-Pad16)") (class "Default")
      (node (ref "U3") (pin "16") (pinfunction "CSB_16") (pintype "bidirectional"))
    )
    (net (code "128") (name "unconnected-(U3-CTS-Pad3)") (class "Default")
      (node (ref "U3") (pin "3") (pinfunction "CTS_3") (pintype "bidirectional"))
    )
    (net (code "129") (name "unconnected-(U3-GND1-Pad21)") (class "Default")
      (node (ref "U3") (pin "21") (pinfunction "GND1_21") (pintype "bidirectional"))
    )
    (net (code "130") (name "unconnected-(U3-GND2-Pad22)") (class "Default")
      (node (ref "U3") (pin "22") (pinfunction "GND2_22") (pintype "bidirectional"))
    )
    (net (code "131") (name "unconnected-(U3-MISO-Pad18)") (class "Default")
      (node (ref "U3") (pin "18") (pinfunction "MISO_18") (pintype "bidirectional"))
    )
    (net (code "132") (name "unconnected-(U3-MOSI-Pad17)") (class "Default")
      (node (ref "U3") (pin "17") (pinfunction "MOSI_17") (pintype "bidirectional"))
    )
    (net (code "133") (name "unconnected-(U3-NC-Pad14)") (class "Default")
      (node (ref "U3") (pin "14") (pinfunction "NC_14") (pintype "bidirectional"))
    )
    (net (code "134") (name "unconnected-(U3-PCM_CLK-Pad5)") (class "Default")
      (node (ref "U3") (pin "5") (pinfunction "PCM_CLK_5") (pintype "bidirectional"))
    )
    (net (code "135") (name "unconnected-(U3-PCM_IN-Pad7)") (class "Default")
      (node (ref "U3") (pin "7") (pinfunction "PCM_IN_7") (pintype "bidirectional"))
    )
    (net (code "136") (name "unconnected-(U3-PCM_OUT-Pad6)") (class "Default")
      (node (ref "U3") (pin "6") (pinfunction "PCM_OUT_6") (pintype "bidirectional"))
    )
    (net (code "137") (name "unconnected-(U3-PCN_SYNC-Pad8)") (class "Default")
      (node (ref "U3") (pin "8") (pinfunction "PCN_SYNC_8") (pintype "bidirectional"))
    )
    (net (code "138") (name "unconnected-(U3-PIO0-Pad23)") (class "Default")
      (node (ref "U3") (pin "23") (pinfunction "PIO0_23") (pintype "bidirectional"))
    )
    (net (code "139") (name "unconnected-(U3-PIO1-Pad24)") (class "Default")
      (node (ref "U3") (pin "24") (pinfunction "PIO1_24") (pintype "bidirectional"))
    )
    (net (code "140") (name "unconnected-(U3-PIO2-Pad25)") (class "Default")
      (node (ref "U3") (pin "25") (pinfunction "PIO2_25") (pintype "bidirectional"))
    )
    (net (code "141") (name "unconnected-(U3-PIO3-Pad26)") (class "Default")
      (node (ref "U3") (pin "26") (pinfunction "PIO3_26") (pintype "bidirectional"))
    )
    (net (code "142") (name "unconnected-(U3-PIO4-Pad27)") (class "Default")
      (node (ref "U3") (pin "27") (pinfunction "PIO4_27") (pintype "bidirectional"))
    )
    (net (code "143") (name "unconnected-(U3-PIO5-Pad28)") (class "Default")
      (node (ref "U3") (pin "28") (pinfunction "PIO5_28") (pintype "bidirectional"))
    )
    (net (code "144") (name "unconnected-(U3-PIO6-Pad29)") (class "Default")
      (node (ref "U3") (pin "29") (pinfunction "PIO6_29") (pintype "bidirectional"))
    )
    (net (code "145") (name "unconnected-(U3-PIO7-Pad30)") (class "Default")
      (node (ref "U3") (pin "30") (pinfunction "PIO7_30") (pintype "bidirectional"))
    )
    (net (code "146") (name "unconnected-(U3-PIO8-Pad31)") (class "Default")
      (node (ref "U3") (pin "31") (pinfunction "PIO8_31") (pintype "bidirectional"))
    )
    (net (code "147") (name "unconnected-(U3-PIO9-Pad32)") (class "Default")
      (node (ref "U3") (pin "32") (pinfunction "PIO9_32") (pintype "bidirectional"))
    )
    (net (code "148") (name "unconnected-(U3-PIO10-Pad33)") (class "Default")
      (node (ref "U3") (pin "33") (pinfunction "PIO10_33") (pintype "bidirectional"))
    )
    (net (code "149") (name "unconnected-(U3-PIO11-Pad34)") (class "Default")
      (node (ref "U3") (pin "34") (pinfunction "PIO11_34") (pintype "bidirectional"))
    )
    (net (code "150") (name "unconnected-(U3-RST-Pad11)") (class "Default")
      (node (ref "U3") (pin "11") (pinfunction "RST_11") (pintype "bidirectional"))
    )
    (net (code "151") (name "unconnected-(U3-RTS-Pad4)") (class "Default")
      (node (ref "U3") (pin "4") (pinfunction "RTS_4") (pintype "bidirectional"))
    )
    (net (code "152") (name "unconnected-(U3-VBUSD+-Pad20)") (class "Default")
      (node (ref "U3") (pin "20") (pinfunction "VBUSD+_20") (pintype "bidirectional"))
    )
    (net (code "153") (name "unconnected-(U3-VBUSD--Pad15)") (class "Default")
      (node (ref "U3") (pin "15") (pinfunction "VBUSD-_15") (pintype "bidirectional"))
    )
  )
)
